# PowerSupply_5V_v1.net
KiCad netlist of a schematic drawn in EAGLE
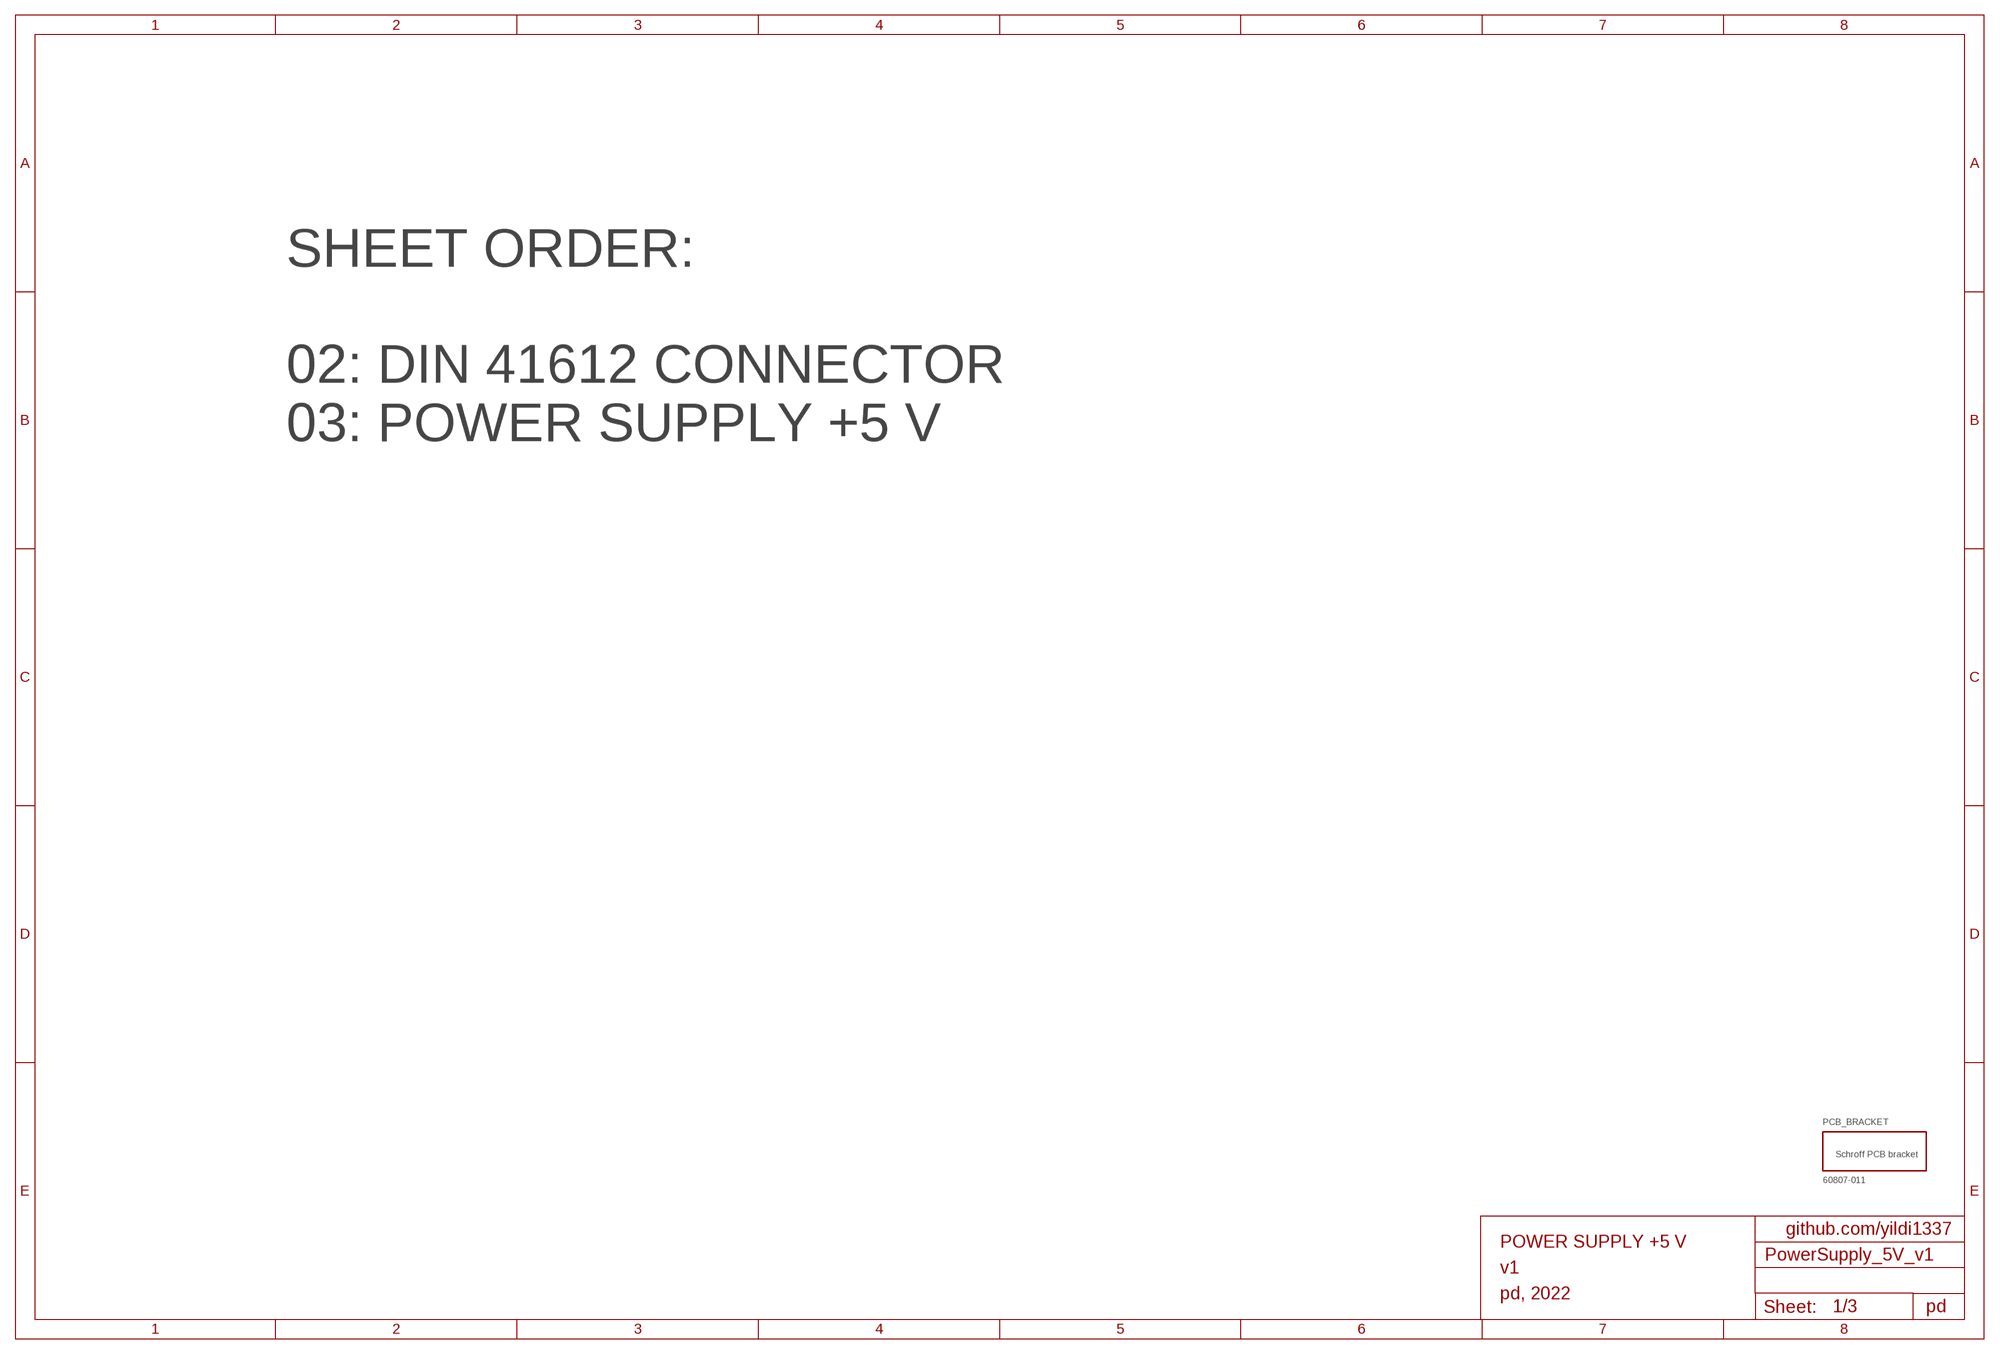
[diagram p0: schematic, sheet 1]
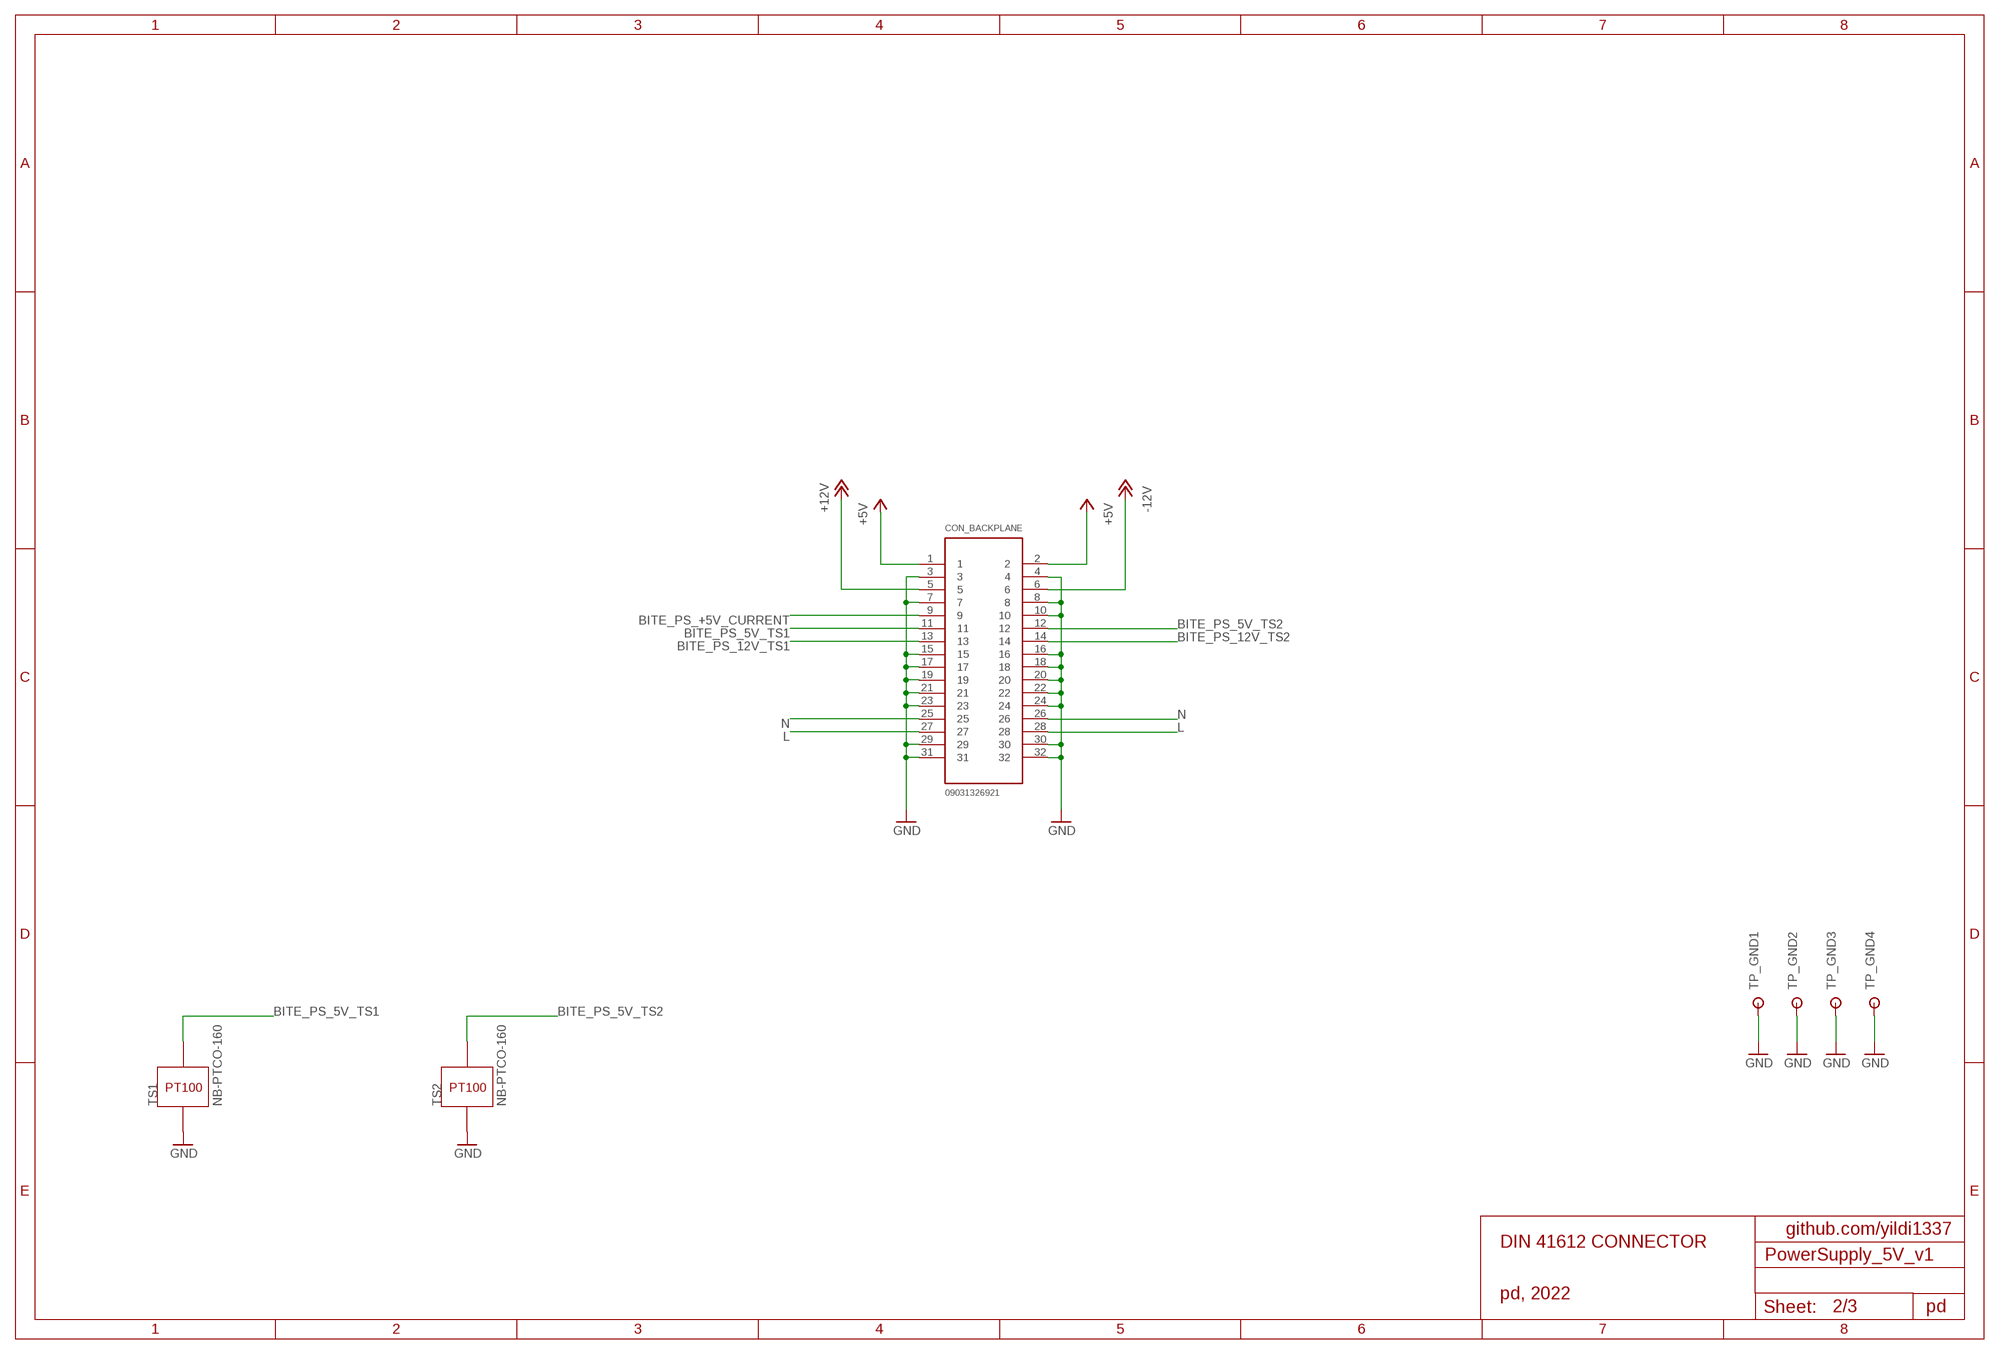
[diagram p1: schematic, sheet 2]
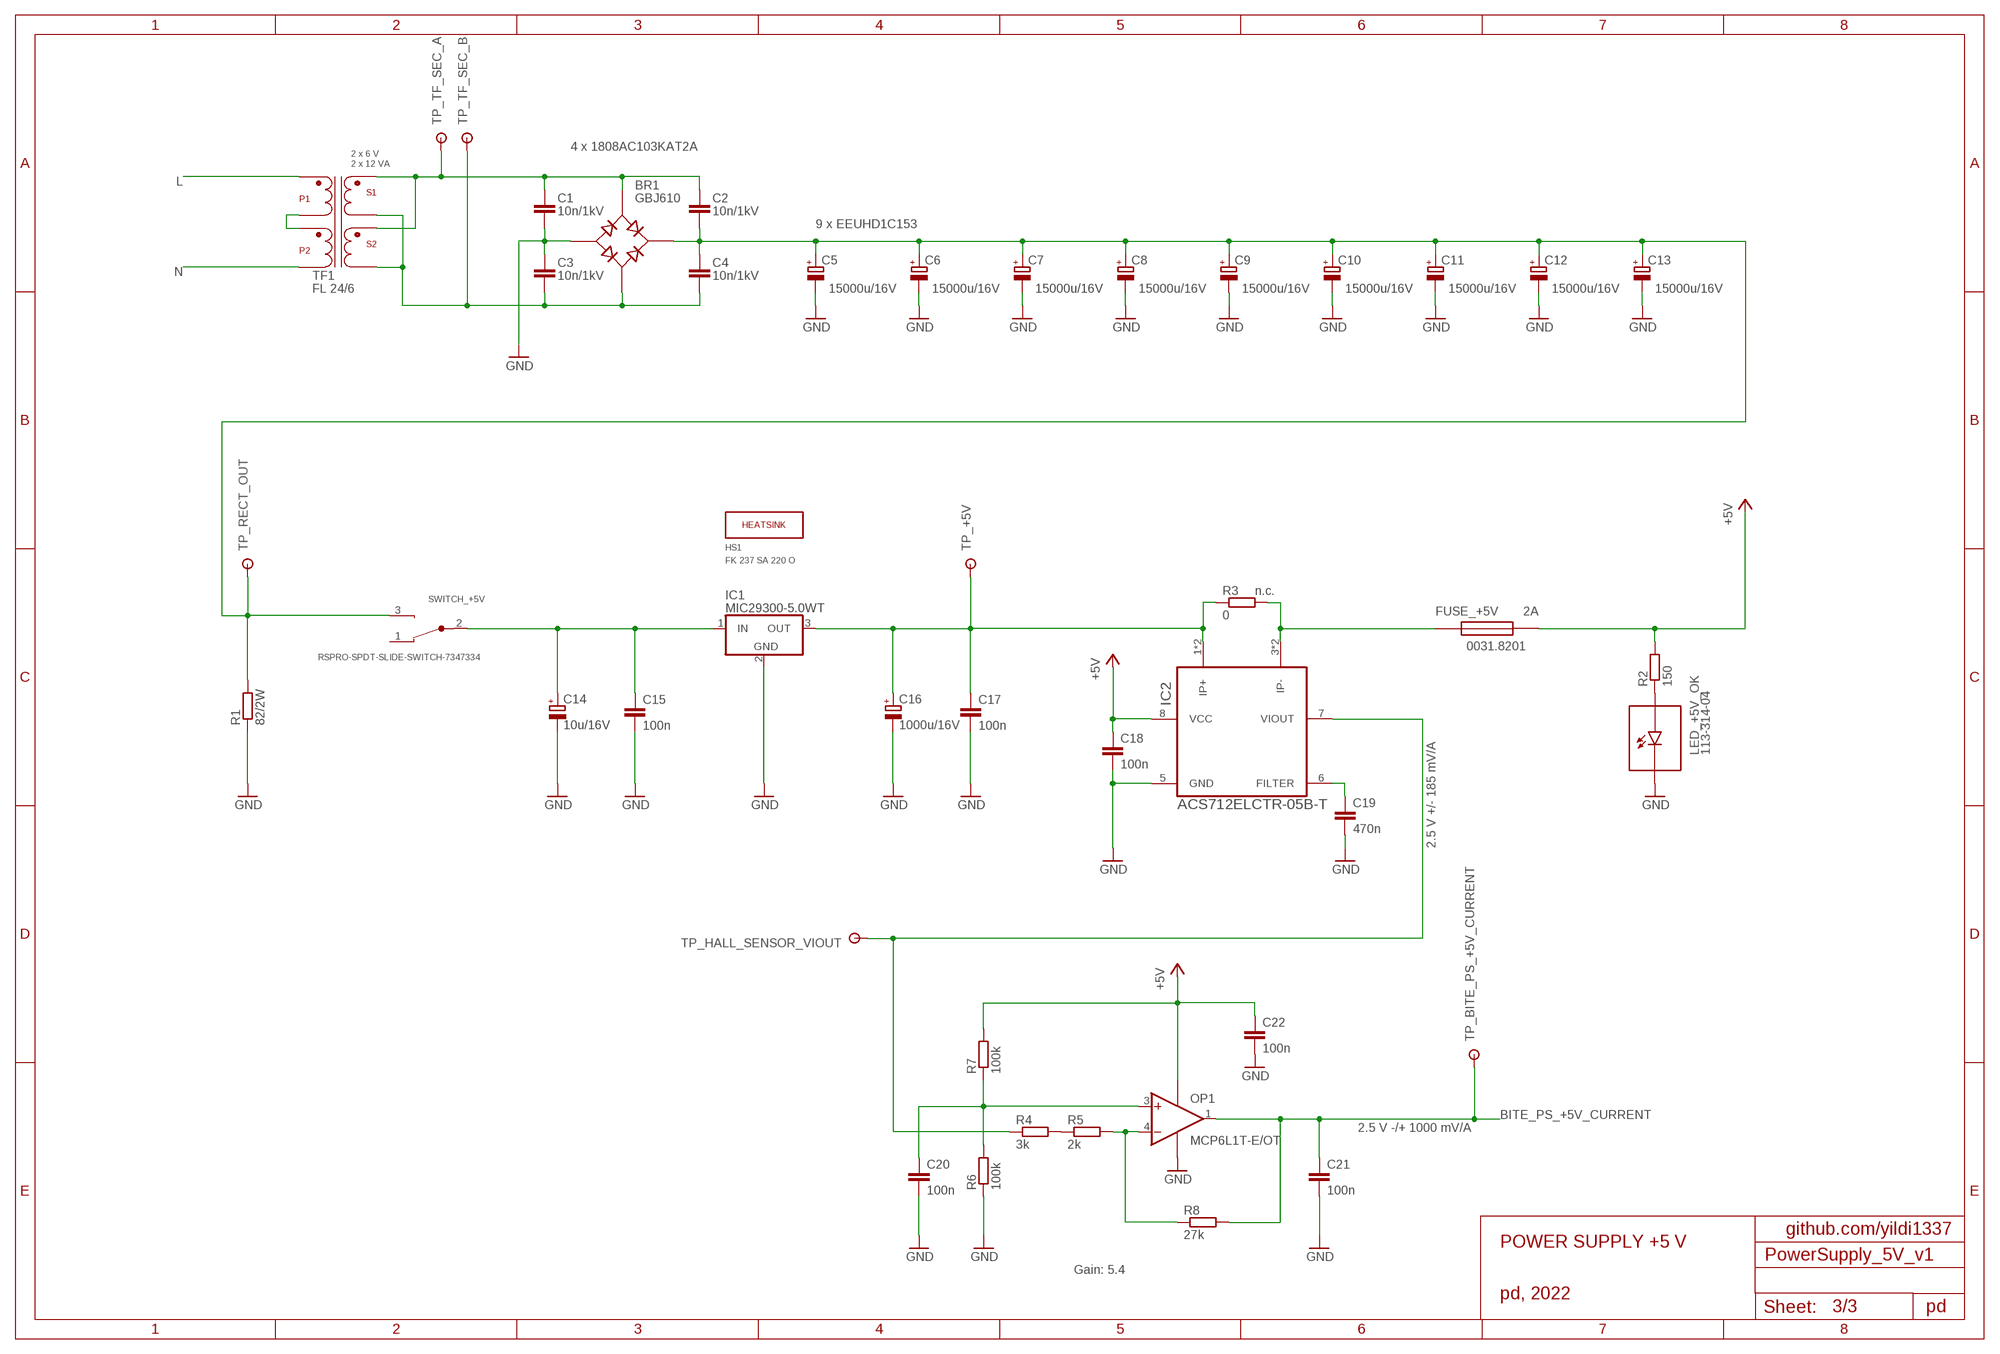
[diagram p2: schematic, sheet 3]

(export (version "E")
  (design (tool "Eeschema 10.0.6"))
  (components
    (comp (ref "CON_BACKPLANE")
      (value "09031326921")
      (footprint "eagle-import:09031326921")
      (libsource (lib "eagle-import") (part "09031326921"))
    )
    (comp (ref "TP_GND1")
      (value "RSPRO-1MM-TERMINAL-POST-2622034")
      (footprint "eagle-import:RSPRO-1MM-TERMINAL-POST-2622034")
      (libsource (lib "eagle-import") (part "RSPRO-1MM-TERMINAL-POST-2622034"))
    )
    (comp (ref "TP_GND2")
      (value "RSPRO-1MM-TERMINAL-POST-2622034")
      (footprint "eagle-import:RSPRO-1MM-TERMINAL-POST-2622034")
      (libsource (lib "eagle-import") (part "RSPRO-1MM-TERMINAL-POST-2622034"))
    )
    (comp (ref "TP_GND3")
      (value "RSPRO-1MM-TERMINAL-POST-2622034")
      (footprint "eagle-import:RSPRO-1MM-TERMINAL-POST-2622034")
      (libsource (lib "eagle-import") (part "RSPRO-1MM-TERMINAL-POST-2622034"))
    )
    (comp (ref "TP_GND4")
      (value "RSPRO-1MM-TERMINAL-POST-2622034")
      (footprint "eagle-import:RSPRO-1MM-TERMINAL-POST-2622034")
      (libsource (lib "eagle-import") (part "RSPRO-1MM-TERMINAL-POST-2622034"))
    )
    (comp (ref "TS1")
      (value "NB-PTCO-160")
      (footprint "eagle-import:NB-PTCO-160")
      (libsource (lib "eagle-import") (part "NB-PTCO-160"))
    )
    (comp (ref "TS2")
      (value "NB-PTCO-160")
      (footprint "eagle-import:NB-PTCO-160")
      (libsource (lib "eagle-import") (part "NB-PTCO-160"))
    )
    (comp (ref "PCB_BRACKET")
      (value "60807-011")
      (footprint "eagle-import:60807-011")
      (libsource (lib "eagle-import") (part "60807-011"))
    )
    (comp (ref "BR1")
      (value "GBJ610")
      (footprint "eagle-import:GBJ610")
      (libsource (lib "eagle-import") (part "GBJ610"))
    )
    (comp (ref "C1")
      (value "10n/1kV")
      (footprint "eagle-import:C1808")
      (libsource (lib "eagle-import") (part "C-EUC1808"))
    )
    (comp (ref "C2")
      (value "10n/1kV")
      (footprint "eagle-import:C1808")
      (libsource (lib "eagle-import") (part "C-EUC1808"))
    )
    (comp (ref "C3")
      (value "10n/1kV")
      (footprint "eagle-import:C1808")
      (libsource (lib "eagle-import") (part "C-EUC1808"))
    )
    (comp (ref "C4")
      (value "10n/1kV")
      (footprint "eagle-import:C1808")
      (libsource (lib "eagle-import") (part "C-EUC1808"))
    )
    (comp (ref "C5")
      (value "15000u/16V")
      (footprint "eagle-import:EEUHD1C153")
      (libsource (lib "eagle-import") (part "EEUHD1C153"))
    )
    (comp (ref "C6")
      (value "15000u/16V")
      (footprint "eagle-import:EEUHD1C153")
      (libsource (lib "eagle-import") (part "EEUHD1C153"))
    )
    (comp (ref "C7")
      (value "15000u/16V")
      (footprint "eagle-import:EEUHD1C153")
      (libsource (lib "eagle-import") (part "EEUHD1C153"))
    )
    (comp (ref "C8")
      (value "15000u/16V")
      (footprint "eagle-import:EEUHD1C153")
      (libsource (lib "eagle-import") (part "EEUHD1C153"))
    )
    (comp (ref "C9")
      (value "15000u/16V")
      (footprint "eagle-import:EEUHD1C153")
      (libsource (lib "eagle-import") (part "EEUHD1C153"))
    )
    (comp (ref "C10")
      (value "15000u/16V")
      (footprint "eagle-import:EEUHD1C153")
      (libsource (lib "eagle-import") (part "EEUHD1C153"))
    )
    (comp (ref "C11")
      (value "15000u/16V")
      (footprint "eagle-import:EEUHD1C153")
      (libsource (lib "eagle-import") (part "EEUHD1C153"))
    )
    (comp (ref "C12")
      (value "15000u/16V")
      (footprint "eagle-import:EEUHD1C153")
      (libsource (lib "eagle-import") (part "EEUHD1C153"))
    )
    (comp (ref "C13")
      (value "15000u/16V")
      (footprint "eagle-import:EEUHD1C153")
      (libsource (lib "eagle-import") (part "EEUHD1C153"))
    )
    (comp (ref "C14")
      (value "10u/16V")
      (footprint "eagle-import:153CLV-0405")
      (libsource (lib "eagle-import") (part "CPOL-EU153CLV-0405"))
    )
    (comp (ref "C15")
      (value "100n")
      (footprint "eagle-import:C0603")
      (libsource (lib "eagle-import") (part "C-EUC0603"))
    )
    (comp (ref "C16")
      (value "1000u/16V")
      (footprint "eagle-import:153CLV-1010")
      (libsource (lib "eagle-import") (part "CPOL-EU153CLV-1010"))
    )
    (comp (ref "C17")
      (value "100n")
      (footprint "eagle-import:C0603")
      (libsource (lib "eagle-import") (part "C-EUC0603"))
    )
    (comp (ref "C18")
      (value "100n")
      (footprint "eagle-import:C0603")
      (libsource (lib "eagle-import") (part "C-EUC0603"))
    )
    (comp (ref "C19")
      (value "470n")
      (footprint "eagle-import:C0603")
      (libsource (lib "eagle-import") (part "C-EUC0603"))
    )
    (comp (ref "C20")
      (value "100n")
      (footprint "eagle-import:C0603")
      (libsource (lib "eagle-import") (part "C-EUC0603"))
    )
    (comp (ref "C21")
      (value "100n")
      (footprint "eagle-import:C0603")
      (libsource (lib "eagle-import") (part "C-EUC0603"))
    )
    (comp (ref "C22")
      (value "100n")
      (footprint "eagle-import:C0603")
      (libsource (lib "eagle-import") (part "C-EUC0603"))
    )
    (comp (ref "FUSE_+5V")
      (value "0031.8201")
      (footprint "eagle-import:0031.8201")
      (libsource (lib "eagle-import") (part "0031.8201"))
    )
    (comp (ref "HS1")
      (value "FK 237 SA 220 O")
      (footprint "eagle-import:FK_237_SA_220_O")
      (libsource (lib "eagle-import") (part "FK_237_SA_220_O"))
    )
    (comp (ref "IC1")
      (value "MIC29300-5.0WT")
      (footprint "eagle-import:MIC29300-5.0WT")
      (libsource (lib "eagle-import") (part "MIC29300-5.0WT"))
    )
    (comp (ref "IC2")
      (value "ACS712ELCTR-05B-T")
      (footprint "eagle-import:ACS712ELCTR-05B-T")
      (libsource (lib "eagle-import") (part "ACS712ELCTR-05B-T"))
    )
    (comp (ref "LED_+5V_OK")
      (value "113-314-04")
      (footprint "eagle-import:113-314-04")
      (libsource (lib "eagle-import") (part "113-314-04"))
    )
    (comp (ref "OP1")
      (value "MCP6L1T-E/OT")
      (footprint "eagle-import:MCP6L1T-E_OT")
      (libsource (lib "eagle-import") (part "MCP6L1T-E/OT"))
    )
    (comp (ref "R1")
      (value "82/2W")
      (footprint "eagle-import:R2010")
      (libsource (lib "eagle-import") (part "R-EU_R2010"))
    )
    (comp (ref "R2")
      (value "150")
      (footprint "eagle-import:R0603")
      (libsource (lib "eagle-import") (part "R-EU_R0603"))
    )
    (comp (ref "R3")
      (value "0")
      (footprint "eagle-import:R0603")
      (libsource (lib "eagle-import") (part "R-EU_R0603"))
    )
    (comp (ref "R4")
      (value "3k")
      (footprint "eagle-import:R0603")
      (libsource (lib "eagle-import") (part "R-EU_R0603"))
    )
    (comp (ref "R5")
      (value "2k")
      (footprint "eagle-import:R0603")
      (libsource (lib "eagle-import") (part "R-EU_R0603"))
    )
    (comp (ref "R6")
      (value "100k")
      (footprint "eagle-import:R0603")
      (libsource (lib "eagle-import") (part "R-EU_R0603"))
    )
    (comp (ref "R7")
      (value "100k")
      (footprint "eagle-import:R0603")
      (libsource (lib "eagle-import") (part "R-EU_R0603"))
    )
    (comp (ref "R8")
      (value "27k")
      (footprint "eagle-import:R0603")
      (libsource (lib "eagle-import") (part "R-EU_R0603"))
    )
    (comp (ref "SWITCH_+5V")
      (value "RSPRO-SPDT-SLIDE-SWITCH-7347334")
      (footprint "eagle-import:RSPRO-SPDT-SLIDE-SWITCH-7347334")
      (libsource (lib "eagle-import") (part "RSPRO-SPDT-SLIDE-SWITCH-7347334"))
    )
    (comp (ref "TF1")
      (value "FL 24/6")
      (footprint "eagle-import:FL_24-6")
      (libsource (lib "eagle-import") (part "FL_24-6"))
    )
    (comp (ref "TP_+5V")
      (value "RSPRO-1MM-TERMINAL-POST-2622034")
      (footprint "eagle-import:RSPRO-1MM-TERMINAL-POST-2622034")
      (libsource (lib "eagle-import") (part "RSPRO-1MM-TERMINAL-POST-2622034"))
    )
    (comp (ref "TP_BITE_PS_+5V_CURRENT")
      (value "RSPRO-1MM-TERMINAL-POST-2622034")
      (footprint "eagle-import:RSPRO-1MM-TERMINAL-POST-2622034")
      (libsource (lib "eagle-import") (part "RSPRO-1MM-TERMINAL-POST-2622034"))
    )
    (comp (ref "TP_HALL_SENSOR_VIOUT")
      (value "RSPRO-1MM-TERMINAL-POST-2622034")
      (footprint "eagle-import:RSPRO-1MM-TERMINAL-POST-2622034")
      (libsource (lib "eagle-import") (part "RSPRO-1MM-TERMINAL-POST-2622034"))
    )
    (comp (ref "TP_RECT_OUT")
      (value "RSPRO-1MM-TERMINAL-POST-2622034")
      (footprint "eagle-import:RSPRO-1MM-TERMINAL-POST-2622034")
      (libsource (lib "eagle-import") (part "RSPRO-1MM-TERMINAL-POST-2622034"))
    )
    (comp (ref "TP_TF_SEC_A")
      (value "RSPRO-1MM-TERMINAL-POST-2622034")
      (footprint "eagle-import:RSPRO-1MM-TERMINAL-POST-2622034")
      (libsource (lib "eagle-import") (part "RSPRO-1MM-TERMINAL-POST-2622034"))
    )
    (comp (ref "TP_TF_SEC_B")
      (value "RSPRO-1MM-TERMINAL-POST-2622034")
      (footprint "eagle-import:RSPRO-1MM-TERMINAL-POST-2622034")
      (libsource (lib "eagle-import") (part "RSPRO-1MM-TERMINAL-POST-2622034"))
    )
  )
  (nets
    (net (code "1") (name "+5V") (class "Default")
      (node (ref "C18") (pin "1") (pinfunction "1_1") (pintype "passive"))
      (node (ref "C22") (pin "1") (pinfunction "1_1") (pintype "passive"))
      (node (ref "CON_BACKPLANE") (pin "1") (pinfunction "1_1") (pintype "bidirectional"))
      (node (ref "CON_BACKPLANE") (pin "2") (pinfunction "2_2") (pintype "bidirectional"))
      (node (ref "FUSE_+5V") (pin "2") (pinfunction "P$2_2") (pintype "bidirectional"))
      (node (ref "IC2") (pin "8") (pinfunction "VCC_8") (pintype "power_in"))
      (node (ref "OP1") (pin "2") (pinfunction "VDD_2") (pintype "power_in"))
      (node (ref "R2") (pin "2") (pinfunction "2_2") (pintype "passive"))
      (node (ref "R7") (pin "2") (pinfunction "2_2") (pintype "passive"))
    )
    (net (code "2") (name "+12V") (class "Default")
      (node (ref "CON_BACKPLANE") (pin "5") (pinfunction "5_5") (pintype "bidirectional"))
    )
    (net (code "3") (name "-12V") (class "Default")
      (node (ref "CON_BACKPLANE") (pin "6") (pinfunction "6_6") (pintype "bidirectional"))
    )
    (net (code "4") (name "BITE_PS_+5V_CURRENT") (class "Default")
      (node (ref "C21") (pin "1") (pinfunction "1_1") (pintype "passive"))
      (node (ref "CON_BACKPLANE") (pin "9") (pinfunction "9_9") (pintype "bidirectional"))
      (node (ref "OP1") (pin "1") (pinfunction "VOUT_1") (pintype "output"))
      (node (ref "R8") (pin "2") (pinfunction "2_2") (pintype "passive"))
      (node (ref "TP_BITE_PS_+5V_CURRENT") (pin "P$1") (pinfunction "P$1_P$1") (pintype "bidirectional"))
    )
    (net (code "5") (name "BITE_PS_5V_TS1") (class "Default")
      (node (ref "CON_BACKPLANE") (pin "11") (pinfunction "11_11") (pintype "bidirectional"))
      (node (ref "TS1") (pin "1") (pinfunction "P$1_1") (pintype "passive"))
    )
    (net (code "6") (name "BITE_PS_5V_TS2") (class "Default")
      (node (ref "CON_BACKPLANE") (pin "12") (pinfunction "12_12") (pintype "bidirectional"))
      (node (ref "TS2") (pin "1") (pinfunction "P$1_1") (pintype "passive"))
    )
    (net (code "7") (name "BITE_PS_12V_TS1") (class "Default")
      (node (ref "CON_BACKPLANE") (pin "13") (pinfunction "13_13") (pintype "bidirectional"))
    )
    (net (code "8") (name "BITE_PS_12V_TS2") (class "Default")
      (node (ref "CON_BACKPLANE") (pin "14") (pinfunction "14_14") (pintype "bidirectional"))
    )
    (net (code "9") (name "GND") (class "Default")
      (node (ref "BR1") (pin "-") (pinfunction "-_-") (pintype "bidirectional"))
      (node (ref "C1") (pin "2") (pinfunction "2_2") (pintype "passive"))
      (node (ref "C10") (pin "-") (pinfunction "-_-") (pintype "passive"))
      (node (ref "C11") (pin "-") (pinfunction "-_-") (pintype "passive"))
      (node (ref "C12") (pin "-") (pinfunction "-_-") (pintype "passive"))
      (node (ref "C13") (pin "-") (pinfunction "-_-") (pintype "passive"))
      (node (ref "C14") (pin "-") (pinfunction "-_-") (pintype "passive"))
      (node (ref "C15") (pin "2") (pinfunction "2_2") (pintype "passive"))
      (node (ref "C16") (pin "-") (pinfunction "-_-") (pintype "passive"))
      (node (ref "C17") (pin "2") (pinfunction "2_2") (pintype "passive"))
      (node (ref "C18") (pin "2") (pinfunction "2_2") (pintype "passive"))
      (node (ref "C19") (pin "2") (pinfunction "2_2") (pintype "passive"))
      (node (ref "C20") (pin "2") (pinfunction "2_2") (pintype "passive"))
      (node (ref "C21") (pin "2") (pinfunction "2_2") (pintype "passive"))
      (node (ref "C22") (pin "2") (pinfunction "2_2") (pintype "passive"))
      (node (ref "C3") (pin "1") (pinfunction "1_1") (pintype "passive"))
      (node (ref "C5") (pin "-") (pinfunction "-_-") (pintype "passive"))
      (node (ref "C6") (pin "-") (pinfunction "-_-") (pintype "passive"))
      (node (ref "C7") (pin "-") (pinfunction "-_-") (pintype "passive"))
      (node (ref "C8") (pin "-") (pinfunction "-_-") (pintype "passive"))
      (node (ref "C9") (pin "-") (pinfunction "-_-") (pintype "passive"))
      (node (ref "CON_BACKPLANE") (pin "10") (pinfunction "10_10") (pintype "bidirectional"))
      (node (ref "CON_BACKPLANE") (pin "15") (pinfunction "15_15") (pintype "bidirectional"))
      (node (ref "CON_BACKPLANE") (pin "16") (pinfunction "16_16") (pintype "bidirectional"))
      (node (ref "CON_BACKPLANE") (pin "17") (pinfunction "17_17") (pintype "bidirectional"))
      (node (ref "CON_BACKPLANE") (pin "18") (pinfunction "18_18") (pintype "bidirectional"))
      (node (ref "CON_BACKPLANE") (pin "19") (pinfunction "19_19") (pintype "bidirectional"))
      (node (ref "CON_BACKPLANE") (pin "20") (pinfunction "20_20") (pintype "bidirectional"))
      (node (ref "CON_BACKPLANE") (pin "21") (pinfunction "21_21") (pintype "bidirectional"))
      (node (ref "CON_BACKPLANE") (pin "22") (pinfunction "22_22") (pintype "bidirectional"))
      (node (ref "CON_BACKPLANE") (pin "23") (pinfunction "23_23") (pintype "bidirectional"))
      (node (ref "CON_BACKPLANE") (pin "24") (pinfunction "24_24") (pintype "bidirectional"))
      (node (ref "CON_BACKPLANE") (pin "29") (pinfunction "29_29") (pintype "bidirectional"))
      (node (ref "CON_BACKPLANE") (pin "3") (pinfunction "3_3") (pintype "bidirectional"))
      (node (ref "CON_BACKPLANE") (pin "30") (pinfunction "30_30") (pintype "bidirectional"))
      (node (ref "CON_BACKPLANE") (pin "31") (pinfunction "31_31") (pintype "bidirectional"))
      (node (ref "CON_BACKPLANE") (pin "32") (pinfunction "32_32") (pintype "bidirectional"))
      (node (ref "CON_BACKPLANE") (pin "4") (pinfunction "4_4") (pintype "bidirectional"))
      (node (ref "CON_BACKPLANE") (pin "7") (pinfunction "7_7") (pintype "bidirectional"))
      (node (ref "CON_BACKPLANE") (pin "8") (pinfunction "8_8") (pintype "bidirectional"))
      (node (ref "IC1") (pin "2") (pinfunction "GND_2") (pintype "passive"))
      (node (ref "IC2") (pin "5") (pinfunction "GND_5") (pintype "power_in"))
      (node (ref "LED_+5V_OK") (pin "-") (pinfunction "C_-") (pintype "passive"))
      (node (ref "OP1") (pin "5") (pinfunction "VSS_5") (pintype "power_in"))
      (node (ref "R1") (pin "1") (pinfunction "1_1") (pintype "passive"))
      (node (ref "R6") (pin "1") (pinfunction "1_1") (pintype "passive"))
      (node (ref "TP_GND1") (pin "P$1") (pinfunction "P$1_P$1") (pintype "bidirectional"))
      (node (ref "TP_GND2") (pin "P$1") (pinfunction "P$1_P$1") (pintype "bidirectional"))
      (node (ref "TP_GND3") (pin "P$1") (pinfunction "P$1_P$1") (pintype "bidirectional"))
      (node (ref "TP_GND4") (pin "P$1") (pinfunction "P$1_P$1") (pintype "bidirectional"))
      (node (ref "TS1") (pin "2") (pinfunction "P$2_2") (pintype "passive"))
      (node (ref "TS2") (pin "2") (pinfunction "P$2_2") (pintype "passive"))
    )
    (net (code "10") (name "L") (class "Default")
      (node (ref "CON_BACKPLANE") (pin "27") (pinfunction "27_27") (pintype "bidirectional"))
      (node (ref "CON_BACKPLANE") (pin "28") (pinfunction "28_28") (pintype "bidirectional"))
      (node (ref "TF1") (pin "P1A") (pinfunction "P1A_P1A") (pintype "passive"))
    )
    (net (code "11") (name "N") (class "Default")
      (node (ref "CON_BACKPLANE") (pin "25") (pinfunction "25_25") (pintype "bidirectional"))
      (node (ref "CON_BACKPLANE") (pin "26") (pinfunction "26_26") (pintype "bidirectional"))
      (node (ref "TF1") (pin "P2B") (pinfunction "P2B_P2B") (pintype "passive"))
    )
    (net (code "12") (name "Net-(BR1-PadL)") (class "Default")
      (node (ref "BR1") (pin "L") (pinfunction "L_L") (pintype "bidirectional"))
      (node (ref "C1") (pin "1") (pinfunction "1_1") (pintype "passive"))
      (node (ref "C2") (pin "1") (pinfunction "1_1") (pintype "passive"))
      (node (ref "TF1") (pin "S1A") (pinfunction "S1A_S1A") (pintype "passive"))
      (node (ref "TF1") (pin "S2A") (pinfunction "S2A_S2A") (pintype "passive"))
      (node (ref "TP_TF_SEC_A") (pin "P$1") (pinfunction "P$1_P$1") (pintype "bidirectional"))
    )
    (net (code "13") (name "Net-(BR1-PadN)") (class "Default")
      (node (ref "BR1") (pin "N") (pinfunction "N_N") (pintype "bidirectional"))
      (node (ref "C3") (pin "2") (pinfunction "2_2") (pintype "passive"))
      (node (ref "C4") (pin "2") (pinfunction "2_2") (pintype "passive"))
      (node (ref "TF1") (pin "S1B") (pinfunction "S1B_S1B") (pintype "passive"))
      (node (ref "TF1") (pin "S2B") (pinfunction "S2B_S2B") (pintype "passive"))
      (node (ref "TP_TF_SEC_B") (pin "P$1") (pinfunction "P$1_P$1") (pintype "bidirectional"))
    )
    (net (code "14") (name "Net-(FUSE_+5V-P$1)") (class "Default")
      (node (ref "FUSE_+5V") (pin "1") (pinfunction "P$1_1") (pintype "bidirectional"))
      (node (ref "IC2") (pin "3") (pinfunction "IP-_3") (pintype "input"))
      (node (ref "IC2") (pin "4") (pinfunction "IP-_4") (pintype "input"))
      (node (ref "R3") (pin "2") (pinfunction "2_2") (pintype "passive"))
    )
    (net (code "15") (name "Net-(IC1-IN)") (class "Default")
      (node (ref "C14") (pin "+") (pinfunction "+_+") (pintype "passive"))
      (node (ref "C15") (pin "1") (pinfunction "1_1") (pintype "passive"))
      (node (ref "IC1") (pin "1") (pinfunction "IN_1") (pintype "input"))
      (node (ref "SWITCH_+5V") (pin "2") (pinfunction "COM_2") (pintype "passive"))
    )
    (net (code "16") (name "Net-(IC1-OUT)") (class "Default")
      (node (ref "C16") (pin "+") (pinfunction "+_+") (pintype "passive"))
      (node (ref "C17") (pin "1") (pinfunction "1_1") (pintype "passive"))
      (node (ref "IC1") (pin "3") (pinfunction "OUT_3") (pintype "passive"))
      (node (ref "IC2") (pin "1") (pinfunction "IP+_1") (pintype "input"))
      (node (ref "IC2") (pin "2") (pinfunction "IP+_2") (pintype "input"))
      (node (ref "R3") (pin "1") (pinfunction "1_1") (pintype "passive"))
      (node (ref "TP_+5V") (pin "P$1") (pinfunction "P$1_P$1") (pintype "bidirectional"))
    )
    (net (code "17") (name "Net-(IC2-FILTER)") (class "Default")
      (node (ref "C19") (pin "1") (pinfunction "1_1") (pintype "passive"))
      (node (ref "IC2") (pin "6") (pinfunction "FILTER_6") (pintype "input"))
    )
    (net (code "18") (name "Net-(IC2-VIOUT)") (class "Default")
      (node (ref "IC2") (pin "7") (pinfunction "VIOUT_7") (pintype "output"))
      (node (ref "R4") (pin "1") (pinfunction "1_1") (pintype "passive"))
      (node (ref "TP_HALL_SENSOR_VIOUT") (pin "P$1") (pinfunction "P$1_P$1") (pintype "bidirectional"))
    )
    (net (code "19") (name "Net-(LED_+5V_OK-A)") (class "Default")
      (node (ref "LED_+5V_OK") (pin "+") (pinfunction "A_+") (pintype "passive"))
      (node (ref "R2") (pin "1") (pinfunction "1_1") (pintype "passive"))
    )
    (net (code "20") (name "Net-(OP1-VIN+)") (class "Default")
      (node (ref "C20") (pin "1") (pinfunction "1_1") (pintype "passive"))
      (node (ref "OP1") (pin "3") (pinfunction "VIN+_3") (pintype "input"))
      (node (ref "R6") (pin "2") (pinfunction "2_2") (pintype "passive"))
      (node (ref "R7") (pin "1") (pinfunction "1_1") (pintype "passive"))
    )
    (net (code "21") (name "Net-(OP1-VIN-)") (class "Default")
      (node (ref "OP1") (pin "4") (pinfunction "VIN-_4") (pintype "input"))
      (node (ref "R5") (pin "2") (pinfunction "2_2") (pintype "passive"))
      (node (ref "R8") (pin "1") (pinfunction "1_1") (pintype "passive"))
    )
    (net (code "22") (name "Net-(R4-Pad2)") (class "Default")
      (node (ref "R4") (pin "2") (pinfunction "2_2") (pintype "passive"))
      (node (ref "R5") (pin "1") (pinfunction "1_1") (pintype "passive"))
    )
    (net (code "23") (name "Net-(SWITCH_+5V-NO)") (class "Default")
      (node (ref "BR1") (pin "+") (pinfunction "+_+") (pintype "bidirectional"))
      (node (ref "C10") (pin "+") (pinfunction "+_+") (pintype "passive"))
      (node (ref "C11") (pin "+") (pinfunction "+_+") (pintype "passive"))
      (node (ref "C12") (pin "+") (pinfunction "+_+") (pintype "passive"))
      (node (ref "C13") (pin "+") (pinfunction "+_+") (pintype "passive"))
      (node (ref "C2") (pin "2") (pinfunction "2_2") (pintype "passive"))
      (node (ref "C4") (pin "1") (pinfunction "1_1") (pintype "passive"))
      (node (ref "C5") (pin "+") (pinfunction "+_+") (pintype "passive"))
      (node (ref "C6") (pin "+") (pinfunction "+_+") (pintype "passive"))
      (node (ref "C7") (pin "+") (pinfunction "+_+") (pintype "passive"))
      (node (ref "C8") (pin "+") (pinfunction "+_+") (pintype "passive"))
      (node (ref "C9") (pin "+") (pinfunction "+_+") (pintype "passive"))
      (node (ref "R1") (pin "2") (pinfunction "2_2") (pintype "passive"))
      (node (ref "SWITCH_+5V") (pin "3") (pinfunction "NO_3") (pintype "passive"))
      (node (ref "TP_RECT_OUT") (pin "P$1") (pinfunction "P$1_P$1") (pintype "bidirectional"))
    )
    (net (code "24") (name "Net-(TF1-PadP1B)") (class "Default")
      (node (ref "TF1") (pin "P1B") (pinfunction "P1B_P1B") (pintype "passive"))
      (node (ref "TF1") (pin "P2A") (pinfunction "P2A_P2A") (pintype "passive"))
    )
    (net (code "25") (name "unconnected-(SWITCH_+5V-NC-Pad1)") (class "Default")
      (node (ref "SWITCH_+5V") (pin "1") (pinfunction "NC_1") (pintype "passive"))
    )
  )
)
